# RotaryConnector_A.net
KiCad netlist of a schematic drawn in EAGLE
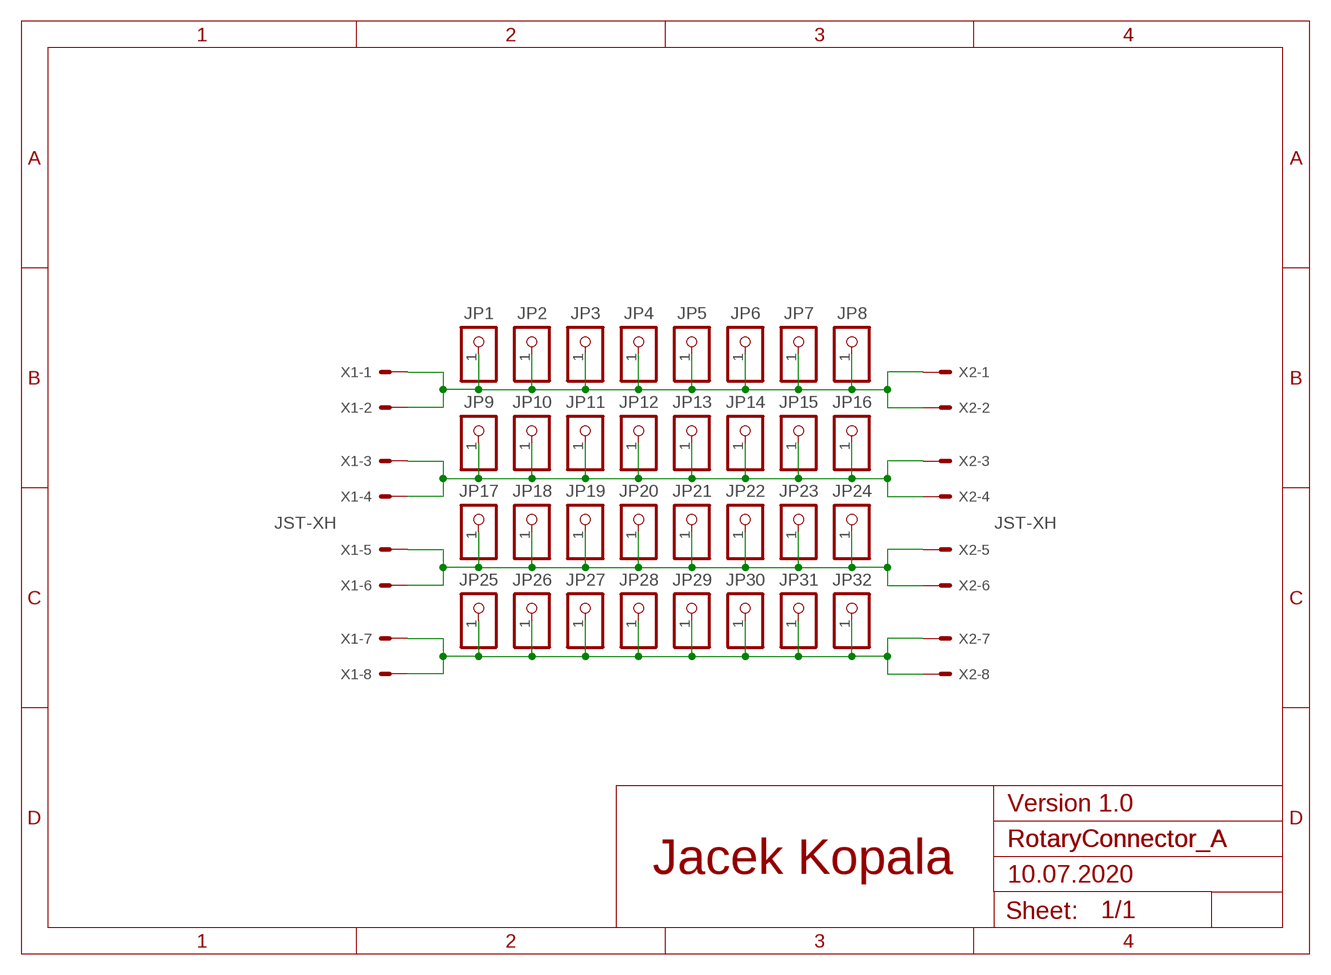
[diagram p0: schematic, sheet 1]

(export (version "E")
  (design (tool "Eeschema 10.0.6"))
  (components
    (comp (ref "JP1")
      (value "PINHD-1X1")
      (footprint "eagle-import:1X01")
      (libsource (lib "eagle-import") (part "PINHD-1X1"))
    )
    (comp (ref "JP2")
      (value "PINHD-1X1")
      (footprint "eagle-import:1X01")
      (libsource (lib "eagle-import") (part "PINHD-1X1"))
    )
    (comp (ref "JP3")
      (value "PINHD-1X1")
      (footprint "eagle-import:1X01")
      (libsource (lib "eagle-import") (part "PINHD-1X1"))
    )
    (comp (ref "JP4")
      (value "PINHD-1X1")
      (footprint "eagle-import:1X01")
      (libsource (lib "eagle-import") (part "PINHD-1X1"))
    )
    (comp (ref "JP5")
      (value "PINHD-1X1")
      (footprint "eagle-import:1X01")
      (libsource (lib "eagle-import") (part "PINHD-1X1"))
    )
    (comp (ref "JP6")
      (value "PINHD-1X1")
      (footprint "eagle-import:1X01")
      (libsource (lib "eagle-import") (part "PINHD-1X1"))
    )
    (comp (ref "JP7")
      (value "PINHD-1X1")
      (footprint "eagle-import:1X01")
      (libsource (lib "eagle-import") (part "PINHD-1X1"))
    )
    (comp (ref "JP8")
      (value "PINHD-1X1")
      (footprint "eagle-import:1X01")
      (libsource (lib "eagle-import") (part "PINHD-1X1"))
    )
    (comp (ref "JP9")
      (value "PINHD-1X1")
      (footprint "eagle-import:1X01")
      (libsource (lib "eagle-import") (part "PINHD-1X1"))
    )
    (comp (ref "JP10")
      (value "PINHD-1X1")
      (footprint "eagle-import:1X01")
      (libsource (lib "eagle-import") (part "PINHD-1X1"))
    )
    (comp (ref "JP11")
      (value "PINHD-1X1")
      (footprint "eagle-import:1X01")
      (libsource (lib "eagle-import") (part "PINHD-1X1"))
    )
    (comp (ref "JP12")
      (value "PINHD-1X1")
      (footprint "eagle-import:1X01")
      (libsource (lib "eagle-import") (part "PINHD-1X1"))
    )
    (comp (ref "JP13")
      (value "PINHD-1X1")
      (footprint "eagle-import:1X01")
      (libsource (lib "eagle-import") (part "PINHD-1X1"))
    )
    (comp (ref "JP14")
      (value "PINHD-1X1")
      (footprint "eagle-import:1X01")
      (libsource (lib "eagle-import") (part "PINHD-1X1"))
    )
    (comp (ref "JP15")
      (value "PINHD-1X1")
      (footprint "eagle-import:1X01")
      (libsource (lib "eagle-import") (part "PINHD-1X1"))
    )
    (comp (ref "JP16")
      (value "PINHD-1X1")
      (footprint "eagle-import:1X01")
      (libsource (lib "eagle-import") (part "PINHD-1X1"))
    )
    (comp (ref "JP17")
      (value "PINHD-1X1")
      (footprint "eagle-import:1X01")
      (libsource (lib "eagle-import") (part "PINHD-1X1"))
    )
    (comp (ref "JP18")
      (value "PINHD-1X1")
      (footprint "eagle-import:1X01")
      (libsource (lib "eagle-import") (part "PINHD-1X1"))
    )
    (comp (ref "JP19")
      (value "PINHD-1X1")
      (footprint "eagle-import:1X01")
      (libsource (lib "eagle-import") (part "PINHD-1X1"))
    )
    (comp (ref "JP20")
      (value "PINHD-1X1")
      (footprint "eagle-import:1X01")
      (libsource (lib "eagle-import") (part "PINHD-1X1"))
    )
    (comp (ref "JP21")
      (value "PINHD-1X1")
      (footprint "eagle-import:1X01")
      (libsource (lib "eagle-import") (part "PINHD-1X1"))
    )
    (comp (ref "JP22")
      (value "PINHD-1X1")
      (footprint "eagle-import:1X01")
      (libsource (lib "eagle-import") (part "PINHD-1X1"))
    )
    (comp (ref "JP23")
      (value "PINHD-1X1")
      (footprint "eagle-import:1X01")
      (libsource (lib "eagle-import") (part "PINHD-1X1"))
    )
    (comp (ref "JP24")
      (value "PINHD-1X1")
      (footprint "eagle-import:1X01")
      (libsource (lib "eagle-import") (part "PINHD-1X1"))
    )
    (comp (ref "JP25")
      (value "PINHD-1X1")
      (footprint "eagle-import:1X01")
      (libsource (lib "eagle-import") (part "PINHD-1X1"))
    )
    (comp (ref "JP26")
      (value "PINHD-1X1")
      (footprint "eagle-import:1X01")
      (libsource (lib "eagle-import") (part "PINHD-1X1"))
    )
    (comp (ref "JP27")
      (value "PINHD-1X1")
      (footprint "eagle-import:1X01")
      (libsource (lib "eagle-import") (part "PINHD-1X1"))
    )
    (comp (ref "JP28")
      (value "PINHD-1X1")
      (footprint "eagle-import:1X01")
      (libsource (lib "eagle-import") (part "PINHD-1X1"))
    )
    (comp (ref "JP29")
      (value "PINHD-1X1")
      (footprint "eagle-import:1X01")
      (libsource (lib "eagle-import") (part "PINHD-1X1"))
    )
    (comp (ref "JP30")
      (value "PINHD-1X1")
      (footprint "eagle-import:1X01")
      (libsource (lib "eagle-import") (part "PINHD-1X1"))
    )
    (comp (ref "JP31")
      (value "PINHD-1X1")
      (footprint "eagle-import:1X01")
      (libsource (lib "eagle-import") (part "PINHD-1X1"))
    )
    (comp (ref "JP32")
      (value "PINHD-1X1")
      (footprint "eagle-import:1X01")
      (libsource (lib "eagle-import") (part "PINHD-1X1"))
    )
    (comp (ref "X1")
      (value "JST-XH")
      (footprint "eagle-import:JST-XH-08-PACKAGE-LONG-PAD")
      (libsource (lib "eagle-import") (part "JST-XH-08-PIN-LONG-PAD"))
    )
    (comp (ref "X2")
      (value "JST-XH")
      (footprint "eagle-import:JST-XH-08-PACKAGE-LONG-PAD")
      (libsource (lib "eagle-import") (part "JST-XH-08-PIN-LONG-PAD"))
    )
  )
  (nets
    (net (code "1") (name "Net-(X1A-S)") (class "Default")
      (node (ref "JP1") (pin "1") (pinfunction "1_1") (pintype "passive"))
      (node (ref "JP2") (pin "1") (pinfunction "1_1") (pintype "passive"))
      (node (ref "JP3") (pin "1") (pinfunction "1_1") (pintype "passive"))
      (node (ref "JP4") (pin "1") (pinfunction "1_1") (pintype "passive"))
      (node (ref "JP5") (pin "1") (pinfunction "1_1") (pintype "passive"))
      (node (ref "JP6") (pin "1") (pinfunction "1_1") (pintype "passive"))
      (node (ref "JP7") (pin "1") (pinfunction "1_1") (pintype "passive"))
      (node (ref "JP8") (pin "1") (pinfunction "1_1") (pintype "passive"))
      (node (ref "X1") (pin "1") (pinfunction "S_1") (pintype "passive"))
      (node (ref "X1") (pin "2") (pinfunction "S_2") (pintype "passive"))
      (node (ref "X2") (pin "1") (pinfunction "S_1") (pintype "passive"))
      (node (ref "X2") (pin "2") (pinfunction "S_2") (pintype "passive"))
    )
    (net (code "2") (name "Net-(X1C-S)") (class "Default")
      (node (ref "JP10") (pin "1") (pinfunction "1_1") (pintype "passive"))
      (node (ref "JP11") (pin "1") (pinfunction "1_1") (pintype "passive"))
      (node (ref "JP12") (pin "1") (pinfunction "1_1") (pintype "passive"))
      (node (ref "JP13") (pin "1") (pinfunction "1_1") (pintype "passive"))
      (node (ref "JP14") (pin "1") (pinfunction "1_1") (pintype "passive"))
      (node (ref "JP15") (pin "1") (pinfunction "1_1") (pintype "passive"))
      (node (ref "JP16") (pin "1") (pinfunction "1_1") (pintype "passive"))
      (node (ref "JP9") (pin "1") (pinfunction "1_1") (pintype "passive"))
      (node (ref "X1") (pin "3") (pinfunction "S_3") (pintype "passive"))
      (node (ref "X1") (pin "4") (pinfunction "S_4") (pintype "passive"))
      (node (ref "X2") (pin "3") (pinfunction "S_3") (pintype "passive"))
      (node (ref "X2") (pin "4") (pinfunction "S_4") (pintype "passive"))
    )
    (net (code "3") (name "Net-(X1E-S)") (class "Default")
      (node (ref "JP17") (pin "1") (pinfunction "1_1") (pintype "passive"))
      (node (ref "JP18") (pin "1") (pinfunction "1_1") (pintype "passive"))
      (node (ref "JP19") (pin "1") (pinfunction "1_1") (pintype "passive"))
      (node (ref "JP20") (pin "1") (pinfunction "1_1") (pintype "passive"))
      (node (ref "JP21") (pin "1") (pinfunction "1_1") (pintype "passive"))
      (node (ref "JP22") (pin "1") (pinfunction "1_1") (pintype "passive"))
      (node (ref "JP23") (pin "1") (pinfunction "1_1") (pintype "passive"))
      (node (ref "JP24") (pin "1") (pinfunction "1_1") (pintype "passive"))
      (node (ref "X1") (pin "5") (pinfunction "S_5") (pintype "passive"))
      (node (ref "X1") (pin "6") (pinfunction "S_6") (pintype "passive"))
      (node (ref "X2") (pin "5") (pinfunction "S_5") (pintype "passive"))
      (node (ref "X2") (pin "6") (pinfunction "S_6") (pintype "passive"))
    )
    (net (code "4") (name "Net-(X1G-S)") (class "Default")
      (node (ref "JP25") (pin "1") (pinfunction "1_1") (pintype "passive"))
      (node (ref "JP26") (pin "1") (pinfunction "1_1") (pintype "passive"))
      (node (ref "JP27") (pin "1") (pinfunction "1_1") (pintype "passive"))
      (node (ref "JP28") (pin "1") (pinfunction "1_1") (pintype "passive"))
      (node (ref "JP29") (pin "1") (pinfunction "1_1") (pintype "passive"))
      (node (ref "JP30") (pin "1") (pinfunction "1_1") (pintype "passive"))
      (node (ref "JP31") (pin "1") (pinfunction "1_1") (pintype "passive"))
      (node (ref "JP32") (pin "1") (pinfunction "1_1") (pintype "passive"))
      (node (ref "X1") (pin "7") (pinfunction "S_7") (pintype "passive"))
      (node (ref "X1") (pin "8") (pinfunction "S_8") (pintype "passive"))
      (node (ref "X2") (pin "7") (pinfunction "S_7") (pintype "passive"))
      (node (ref "X2") (pin "8") (pinfunction "S_8") (pintype "passive"))
    )
  )
)
